# base.net
KiCad netlist of a schematic drawn in Altium Designer
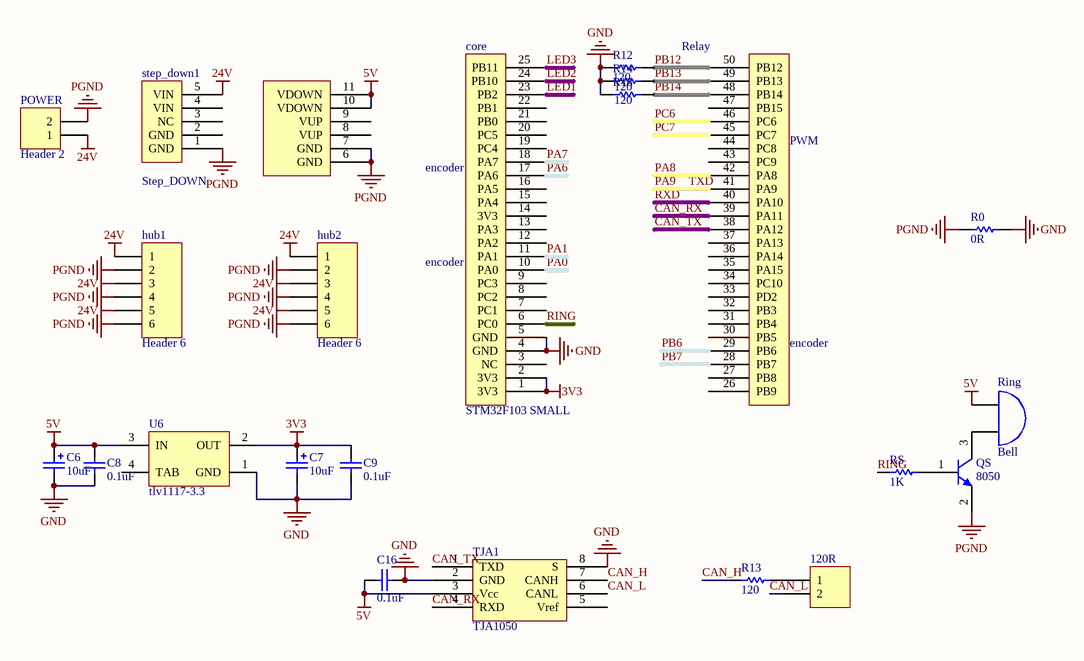
[diagram p0: base.SchDoc]

(export (version "E")
  (design (tool "Eeschema 10.0.6"))
  (components
    (comp (ref "120R")
      (value "Header 2")
      (footprint "SIP2")
      (description "Header, 2-Pin")
      (fields (field (name "PUBLISHER") "Altium Limited"))
      (libsource (lib "Libraries_2014_0618") (part "Header 2"))
    )
    (comp (ref "C6")
      (value "10uF")
      (footprint "6032C")
      (description "Polarized Capacitor (Radial)")
      (fields (field (name "Comment") "Cap Pol1") (field (name "PUBLISHER") "Altium Limited"))
      (libsource (lib "K60-mainboard-v3.1") (part "Cap Pol1"))
    )
    (comp (ref "C7")
      (value "10uF")
      (footprint "6032C")
      (description "Polarized Capacitor (Radial)")
      (fields (field (name "Comment") "Cap Pol1") (field (name "PUBLISHER") "Altium Limited"))
      (libsource (lib "K60-mainboard-v3.1") (part "Cap Pol1"))
    )
    (comp (ref "C8")
      (value "0.1uF")
      (footprint "CAP-MLCC-0603")
      (description "Capacitor")
      (fields (field (name "Comment") "Cap") (field (name "PUBLISHER") "Altium Limited"))
      (libsource (lib "K60-mainboard-v3.1") (part "Cap"))
    )
    (comp (ref "C9")
      (value "0.1uF")
      (footprint "CAP-MLCC-0603")
      (description "Capacitor")
      (fields (field (name "Comment") "Cap") (field (name "PUBLISHER") "Altium Limited"))
      (libsource (lib "K60-mainboard-v3.1") (part "Cap"))
    )
    (comp (ref "C16")
      (value "0.1uF")
      (footprint "CAP-MLCC-0603")
      (description "Capacitor")
      (fields (field (name "Comment") "Cap") (field (name "PUBLISHER") "Altium Limited"))
      (libsource (lib "K60-mainboard-v3.1") (part "Cap"))
    )
    (comp (ref "core")
      (value "STM32F103 SMALL")
      (footprint "STM32F103Small")
      (libsource (lib "K60-mainboard-v3.1") (part "STM32F103 SMALL"))
    )
    (comp (ref "hub1")
      (value "Header 6")
      (footprint "Green_6P")
      (description "Header, 6-Pin")
      (fields (field (name "PUBLISHER") "Altium Limited"))
      (libsource (lib "Libraries_2014_0618") (part "Header 6"))
    )
    (comp (ref "hub2")
      (value "Header 6")
      (footprint "Green_6P")
      (description "Header, 6-Pin")
      (fields (field (name "PUBLISHER") "Altium Limited"))
      (libsource (lib "Libraries_2014_0618") (part "Header 6"))
    )
    (comp (ref "POWER")
      (value "Header 2")
      (footprint "Green_2P")
      (description "Header, 2-Pin")
      (fields (field (name "PUBLISHER") "Altium Limited"))
      (libsource (lib "K60-mainboard-v3.1") (part "Header 2"))
    )
    (comp (ref "QS")
      (value "8050")
      (footprint "SOT-23B_N")
      (description "NPN Bipolar Transistor")
      (fields (field (name "PUBLISHER") "Altium Limited"))
      (libsource (lib "附加元件") (part "QNPN"))
    )
    (comp (ref "R0")
      (value "0R")
      (footprint "RES-0603")
      (description "Resistor")
      (fields (field (name "Comment") "Res1") (field (name "PUBLISHER") "Altium Limited"))
      (libsource (lib "K60-mainboard-v3.1") (part "Res1"))
    )
    (comp (ref "R12")
      (value "120")
      (footprint "RES-0603")
      (description "Resistor")
      (fields (field (name "Comment") "Res1") (field (name "PUBLISHER") "Altium Limited"))
      (libsource (lib "K60-mainboard-v3.1") (part "Res1"))
    )
    (comp (ref "R13")
      (value "120")
      (footprint "RES-0603")
      (description "Resistor")
      (fields (field (name "Comment") "Res1") (field (name "PUBLISHER") "Altium Limited"))
      (libsource (lib "K60-mainboard-v3.1") (part "Res1"))
    )
    (comp (ref "R14")
      (value "120")
      (footprint "RES-0603")
      (description "Resistor")
      (fields (field (name "Comment") "Res1") (field (name "PUBLISHER") "Altium Limited"))
      (libsource (lib "K60-mainboard-v3.1") (part "Res1"))
    )
    (comp (ref "R18")
      (value "120")
      (footprint "RES-0603")
      (description "Resistor")
      (fields (field (name "Comment") "Res1") (field (name "PUBLISHER") "Altium Limited"))
      (libsource (lib "K60-mainboard-v3.1") (part "Res1"))
    )
    (comp (ref "Ring")
      (value "Bell")
      (footprint "Ring")
      (description "Electrical Bell")
      (fields (field (name "PUBLISHER") "Altium Limited"))
      (libsource (lib "附加元件") (part "Bell"))
    )
    (comp (ref "RS")
      (value "1K")
      (footprint "RES-0603")
      (description "Resistor")
      (fields (field (name "Comment") "Res1") (field (name "PUBLISHER") "Altium Limited"))
      (libsource (lib "K60-mainboard-v3.1") (part "Res1"))
    )
    (comp (ref "step_down1")
      (value "Step_DOWN")
      (footprint "Step_Up_Down")
      (libsource (lib "K60-mainboard-v3.1") (part "Step_DOWN"))
    )
    (comp (ref "TJA1")
      (value "TJA1050")
      (footprint "TJA1050")
      (description "CAN总线收发器")
      (libsource (lib "Libraries_2014_0618") (part "TJA1050"))
    )
    (comp (ref "U6")
      (value "tlv1117-3.3")
      (footprint "LM1117")
      (description "800mA Low-Dropout Linear Regulator")
      (fields
        (field (name "PARTNUMBER") "LM1117IMP-5.0")
        (field (name "MANUFACTURER") "National Semiconductor")
        (field (name "PUBLISHER") "Altium Limited")
      )
      (libsource (lib "K60-mainboard-v3.1") (part "LM1117IMP-5.0"))
    )
  )
  (nets
    (net (code "1") (name "/CAN_H") (class "Default")
      (node (ref "R13") (pin "2") (pinfunction "2_2") (pintype "passive"))
      (node (ref "TJA1") (pin "7") (pinfunction "CANH_7") (pintype "passive"))
    )
    (net (code "2") (name "/CAN_L") (class "Default")
      (node (ref "120R") (pin "2") (pinfunction "2_2") (pintype "passive"))
      (node (ref "TJA1") (pin "6") (pinfunction "CANL_6") (pintype "passive"))
    )
    (net (code "3") (name "/CAN_RX") (class "Default")
      (node (ref "TJA1") (pin "4") (pinfunction "RXD_4") (pintype "passive"))
      (node (ref "core") (pin "39") (pinfunction "PA11_39") (pintype "passive"))
    )
    (net (code "4") (name "/CAN_TX") (class "Default")
      (node (ref "TJA1") (pin "1") (pinfunction "TXD_1") (pintype "passive"))
      (node (ref "core") (pin "38") (pinfunction "PA12_38") (pintype "passive"))
    )
    (net (code "5") (name "/LED1") (class "Default")
      (node (ref "core") (pin "23") (pinfunction "PB2_23") (pintype "passive"))
    )
    (net (code "6") (name "/LED2") (class "Default")
      (node (ref "core") (pin "24") (pinfunction "PB10_24") (pintype "passive"))
    )
    (net (code "7") (name "/LED3") (class "Default")
      (node (ref "core") (pin "25") (pinfunction "PB11_25") (pintype "passive"))
    )
    (net (code "8") (name "/PA0") (class "Default")
      (node (ref "core") (pin "10") (pinfunction "PA0_10") (pintype "passive"))
    )
    (net (code "9") (name "/PA1") (class "Default")
      (node (ref "core") (pin "11") (pinfunction "PA1_11") (pintype "passive"))
    )
    (net (code "10") (name "/PA6") (class "Default")
      (node (ref "core") (pin "17") (pinfunction "PA6_17") (pintype "passive"))
    )
    (net (code "11") (name "/PA7") (class "Default")
      (node (ref "core") (pin "18") (pinfunction "PA7_18") (pintype "passive"))
    )
    (net (code "12") (name "/PA8") (class "Default")
      (node (ref "core") (pin "42") (pinfunction "PA8_42") (pintype "passive"))
    )
    (net (code "13") (name "/PA9") (class "Default")
      (node (ref "core") (pin "41") (pinfunction "PA9_41") (pintype "passive"))
    )
    (net (code "14") (name "/PB6") (class "Default")
      (node (ref "core") (pin "29") (pinfunction "PB6_29") (pintype "passive"))
    )
    (net (code "15") (name "/PB7") (class "Default")
      (node (ref "core") (pin "28") (pinfunction "PB7_28") (pintype "passive"))
    )
    (net (code "16") (name "/PB12") (class "Default")
      (node (ref "R12") (pin "2") (pinfunction "2_2") (pintype "passive"))
      (node (ref "core") (pin "50") (pinfunction "PB12_50") (pintype "passive"))
    )
    (net (code "17") (name "/PB13") (class "Default")
      (node (ref "R14") (pin "2") (pinfunction "2_2") (pintype "passive"))
      (node (ref "core") (pin "49") (pinfunction "PB13_49") (pintype "passive"))
    )
    (net (code "18") (name "/PB14") (class "Default")
      (node (ref "R18") (pin "2") (pinfunction "2_2") (pintype "passive"))
      (node (ref "core") (pin "48") (pinfunction "PB14_48") (pintype "passive"))
    )
    (net (code "19") (name "/PC6") (class "Default")
      (node (ref "core") (pin "46") (pinfunction "PC6_46") (pintype "passive"))
    )
    (net (code "20") (name "/PC7") (class "Default")
      (node (ref "core") (pin "45") (pinfunction "PC7_45") (pintype "passive"))
    )
    (net (code "21") (name "/RING") (class "Default")
      (node (ref "RS") (pin "2") (pinfunction "2_2") (pintype "passive"))
      (node (ref "core") (pin "6") (pinfunction "PC0_6") (pintype "passive"))
    )
    (net (code "22") (name "/RXD") (class "Default")
      (node (ref "core") (pin "40") (pinfunction "PA10_40") (pintype "passive"))
    )
    (net (code "23") (name "3V3") (class "Default")
      (node (ref "C7") (pin "1") (pinfunction "1_1") (pintype "passive"))
      (node (ref "C9") (pin "2") (pinfunction "2_2") (pintype "passive"))
      (node (ref "U6") (pin "2") (pinfunction "OUT_2") (pintype "power_in"))
      (node (ref "core") (pin "1") (pinfunction "3V3_1") (pintype "passive"))
      (node (ref "core") (pin "2") (pinfunction "3V3_2") (pintype "passive"))
    )
    (net (code "24") (name "5V") (class "Default")
      (node (ref "C16") (pin "1") (pinfunction "1_1") (pintype "passive"))
      (node (ref "C6") (pin "1") (pinfunction "1_1") (pintype "passive"))
      (node (ref "C8") (pin "2") (pinfunction "2_2") (pintype "passive"))
      (node (ref "Ring") (pin "1") (pinfunction "A_1") (pintype "passive"))
      (node (ref "TJA1") (pin "3") (pinfunction "Vcc_3") (pintype "passive"))
      (node (ref "U6") (pin "3") (pinfunction "IN_3") (pintype "power_in"))
      (node (ref "step_down1") (pin "10") (pinfunction "VDOWN_10") (pintype "passive"))
      (node (ref "step_down1") (pin "11") (pinfunction "VDOWN_11") (pintype "passive"))
    )
    (net (code "25") (name "24V") (class "Default")
      (node (ref "POWER") (pin "1") (pinfunction "1_1") (pintype "passive"))
      (node (ref "hub1") (pin "1") (pinfunction "1_1") (pintype "passive"))
      (node (ref "hub1") (pin "3") (pinfunction "3_3") (pintype "passive"))
      (node (ref "hub1") (pin "5") (pinfunction "5_5") (pintype "passive"))
      (node (ref "hub2") (pin "1") (pinfunction "1_1") (pintype "passive"))
      (node (ref "hub2") (pin "3") (pinfunction "3_3") (pintype "passive"))
      (node (ref "hub2") (pin "5") (pinfunction "5_5") (pintype "passive"))
      (node (ref "step_down1") (pin "5") (pinfunction "VIN_5") (pintype "passive"))
    )
    (net (code "26") (name "GND") (class "Default")
      (node (ref "C16") (pin "2") (pinfunction "2_2") (pintype "passive"))
      (node (ref "C6") (pin "2") (pinfunction "2_2") (pintype "passive"))
      (node (ref "C7") (pin "2") (pinfunction "2_2") (pintype "passive"))
      (node (ref "C8") (pin "1") (pinfunction "1_1") (pintype "passive"))
      (node (ref "C9") (pin "1") (pinfunction "1_1") (pintype "passive"))
      (node (ref "R0") (pin "1") (pinfunction "1_1") (pintype "passive"))
      (node (ref "R12") (pin "1") (pinfunction "1_1") (pintype "passive"))
      (node (ref "R14") (pin "1") (pinfunction "1_1") (pintype "passive"))
      (node (ref "R18") (pin "1") (pinfunction "1_1") (pintype "passive"))
      (node (ref "TJA1") (pin "2") (pinfunction "GND_2") (pintype "passive"))
      (node (ref "TJA1") (pin "8") (pinfunction "S_8") (pintype "passive"))
      (node (ref "U6") (pin "1") (pinfunction "GND_1") (pintype "power_in"))
      (node (ref "core") (pin "4") (pinfunction "GND_4") (pintype "passive"))
      (node (ref "core") (pin "5") (pinfunction "GND_5") (pintype "passive"))
    )
    (net (code "27") (name "Net-(120R-Pad1)") (class "Default")
      (node (ref "120R") (pin "1") (pinfunction "1_1") (pintype "passive"))
      (node (ref "R13") (pin "1") (pinfunction "1_1") (pintype "passive"))
    )
    (net (code "28") (name "Net-(QS-B)") (class "Default")
      (node (ref "QS") (pin "1") (pinfunction "B_1") (pintype "passive"))
      (node (ref "RS") (pin "1") (pinfunction "1_1") (pintype "passive"))
    )
    (net (code "29") (name "Net-(QS-C)") (class "Default")
      (node (ref "QS") (pin "3") (pinfunction "C_3") (pintype "passive"))
      (node (ref "Ring") (pin "2") (pinfunction "B_2") (pintype "passive"))
    )
    (net (code "30") (name "PGND") (class "Default")
      (node (ref "POWER") (pin "2") (pinfunction "2_2") (pintype "passive"))
      (node (ref "QS") (pin "2") (pinfunction "E_2") (pintype "passive"))
      (node (ref "R0") (pin "2") (pinfunction "2_2") (pintype "passive"))
      (node (ref "hub1") (pin "2") (pinfunction "2_2") (pintype "passive"))
      (node (ref "hub1") (pin "4") (pinfunction "4_4") (pintype "passive"))
      (node (ref "hub1") (pin "6") (pinfunction "6_6") (pintype "passive"))
      (node (ref "hub2") (pin "2") (pinfunction "2_2") (pintype "passive"))
      (node (ref "hub2") (pin "4") (pinfunction "4_4") (pintype "passive"))
      (node (ref "hub2") (pin "6") (pinfunction "6_6") (pintype "passive"))
      (node (ref "step_down1") (pin "1") (pinfunction "GND_1") (pintype "passive"))
      (node (ref "step_down1") (pin "6") (pinfunction "GND_6") (pintype "passive"))
      (node (ref "step_down1") (pin "7") (pinfunction "GND_7") (pintype "passive"))
    )
    (net (code "31") (name "unconnected-(TJA1-Vref-Pad5)") (class "Default")
      (node (ref "TJA1") (pin "5") (pinfunction "Vref_5") (pintype "passive"))
    )
    (net (code "32") (name "unconnected-(U6-TAB-Pad4)") (class "Default")
      (node (ref "U6") (pin "4") (pinfunction "TAB_4") (pintype "power_in"))
    )
    (net (code "33") (name "unconnected-(core-3V3-Pad14)") (class "Default")
      (node (ref "core") (pin "14") (pinfunction "3V3_14") (pintype "passive"))
    )
    (net (code "34") (name "unconnected-(core-NC-Pad3)") (class "Default")
      (node (ref "core") (pin "3") (pinfunction "NC_3") (pintype "passive"))
    )
    (net (code "35") (name "unconnected-(core-PA2-Pad12)") (class "Default")
      (node (ref "core") (pin "12") (pinfunction "PA2_12") (pintype "passive"))
    )
    (net (code "36") (name "unconnected-(core-PA3-Pad13)") (class "Default")
      (node (ref "core") (pin "13") (pinfunction "PA3_13") (pintype "passive"))
    )
    (net (code "37") (name "unconnected-(core-PA4-Pad15)") (class "Default")
      (node (ref "core") (pin "15") (pinfunction "PA4_15") (pintype "passive"))
    )
    (net (code "38") (name "unconnected-(core-PA5-Pad16)") (class "Default")
      (node (ref "core") (pin "16") (pinfunction "PA5_16") (pintype "passive"))
    )
    (net (code "39") (name "unconnected-(core-PA13-Pad37)") (class "Default")
      (node (ref "core") (pin "37") (pinfunction "PA13_37") (pintype "passive"))
    )
    (net (code "40") (name "unconnected-(core-PA14-Pad36)") (class "Default")
      (node (ref "core") (pin "36") (pinfunction "PA14_36") (pintype "passive"))
    )
    (net (code "41") (name "unconnected-(core-PA15-Pad35)") (class "Default")
      (node (ref "core") (pin "35") (pinfunction "PA15_35") (pintype "passive"))
    )
    (net (code "42") (name "unconnected-(core-PB0-Pad21)") (class "Default")
      (node (ref "core") (pin "21") (pinfunction "PB0_21") (pintype "passive"))
    )
    (net (code "43") (name "unconnected-(core-PB1-Pad22)") (class "Default")
      (node (ref "core") (pin "22") (pinfunction "PB1_22") (pintype "passive"))
    )
    (net (code "44") (name "unconnected-(core-PB3-Pad32)") (class "Default")
      (node (ref "core") (pin "32") (pinfunction "PB3_32") (pintype "passive"))
    )
    (net (code "45") (name "unconnected-(core-PB4-Pad31)") (class "Default")
      (node (ref "core") (pin "31") (pinfunction "PB4_31") (pintype "passive"))
    )
    (net (code "46") (name "unconnected-(core-PB5-Pad30)") (class "Default")
      (node (ref "core") (pin "30") (pinfunction "PB5_30") (pintype "passive"))
    )
    (net (code "47") (name "unconnected-(core-PB8-Pad27)") (class "Default")
      (node (ref "core") (pin "27") (pinfunction "PB8_27") (pintype "passive"))
    )
    (net (code "48") (name "unconnected-(core-PB9-Pad26)") (class "Default")
      (node (ref "core") (pin "26") (pinfunction "PB9_26") (pintype "passive"))
    )
    (net (code "49") (name "unconnected-(core-PB15-Pad47)") (class "Default")
      (node (ref "core") (pin "47") (pinfunction "PB15_47") (pintype "passive"))
    )
    (net (code "50") (name "unconnected-(core-PC1-Pad7)") (class "Default")
      (node (ref "core") (pin "7") (pinfunction "PC1_7") (pintype "passive"))
    )
    (net (code "51") (name "unconnected-(core-PC2-Pad8)") (class "Default")
      (node (ref "core") (pin "8") (pinfunction "PC2_8") (pintype "passive"))
    )
    (net (code "52") (name "unconnected-(core-PC3-Pad9)") (class "Default")
      (node (ref "core") (pin "9") (pinfunction "PC3_9") (pintype "passive"))
    )
    (net (code "53") (name "unconnected-(core-PC4-Pad19)") (class "Default")
      (node (ref "core") (pin "19") (pinfunction "PC4_19") (pintype "passive"))
    )
    (net (code "54") (name "unconnected-(core-PC5-Pad20)") (class "Default")
      (node (ref "core") (pin "20") (pinfunction "PC5_20") (pintype "passive"))
    )
    (net (code "55") (name "unconnected-(core-PC8-Pad44)") (class "Default")
      (node (ref "core") (pin "44") (pinfunction "PC8_44") (pintype "passive"))
    )
    (net (code "56") (name "unconnected-(core-PC9-Pad43)") (class "Default")
      (node (ref "core") (pin "43") (pinfunction "PC9_43") (pintype "passive"))
    )
    (net (code "57") (name "unconnected-(core-PC10-Pad34)") (class "Default")
      (node (ref "core") (pin "34") (pinfunction "PC10_34") (pintype "passive"))
    )
    (net (code "58") (name "unconnected-(core-PD2-Pad33)") (class "Default")
      (node (ref "core") (pin "33") (pinfunction "PD2_33") (pintype "passive"))
    )
    (net (code "59") (name "unconnected-(step_down1-GND-Pad2)") (class "Default")
      (node (ref "step_down1") (pin "2") (pinfunction "GND_2") (pintype "passive"))
    )
    (net (code "60") (name "unconnected-(step_down1-NC-Pad3)") (class "Default")
      (node (ref "step_down1") (pin "3") (pinfunction "NC_3") (pintype "passive"))
    )
    (net (code "61") (name "unconnected-(step_down1-VIN-Pad4)") (class "Default")
      (node (ref "step_down1") (pin "4") (pinfunction "VIN_4") (pintype "passive"))
    )
    (net (code "62") (name "unconnected-(step_down1-VUP-Pad8)") (class "Default")
      (node (ref "step_down1") (pin "8") (pinfunction "VUP_8") (pintype "passive"))
    )
    (net (code "63") (name "unconnected-(step_down1-VUP-Pad9)") (class "Default")
      (node (ref "step_down1") (pin "9") (pinfunction "VUP_9") (pintype "passive"))
    )
  )
)
